# Voeding.net
KiCad netlist of a schematic drawn in Altium Designer
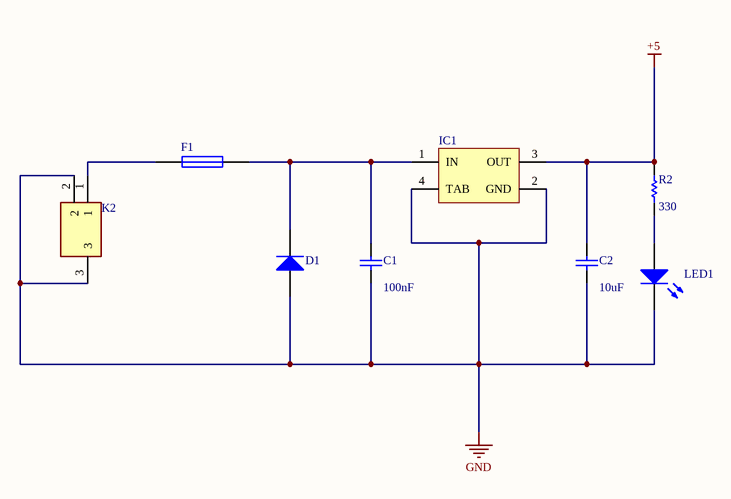
[diagram p0: Voeding.SchDoc]

(export (version "E")
  (design (tool "Eeschema 10.0.6"))
  (components
    (comp (ref "C1")
      (value "100nF")
      (footprint "6-0805_M")
      (description "Capacitor")
      (fields (field (name "Comment") "Cap") (field (name "PUBLISHER") "Altium Limited"))
      (libsource (lib "Miscellaneous Devices") (part "Cap"))
    )
    (comp (ref "C2")
      (value "10uF")
      (footprint "CAP_EEV-FK1K101V")
      (description "Capacitor")
      (fields (field (name "Comment") "Cap") (field (name "PUBLISHER") "Altium Limited"))
      (libsource (lib "Miscellaneous Devices") (part "Cap"))
    )
    (comp (ref "D1")
      (value "Diode 1N4004")
      (footprint "DO-41")
      (description "1 Amp General Purpose Rectifier")
      (fields (field (name "PUBLISHER") "Altium Limited"))
      (libsource (lib "Miscellaneous Devices") (part "Diode 1N4004"))
    )
    (comp (ref "F1")
      (value "Fuse 1")
      (footprint "CAPC3216X94N")
      (description "Fuse")
      (fields (field (name "PUBLISHER") "Altium Limited"))
      (libsource (lib "Miscellaneous Devices") (part "Fuse 1"))
    )
    (comp (ref "IC1")
      (value "LM3940IMP-3.3")
      (footprint "DCY0004A_L")
      (description "1A Low Dropout Regulator for 5V to 3.3V Conversion, 4-pin SOT-223")
      (fields (field (name "MANUFACTURER") "Texas Instruments"))
      (libsource (lib "Altium Content Vault") (part "PM-REG-LM2940-TO4"))
    )
    (comp (ref "K2")
      (value "MJ-180PH")
      (footprint "SamacSys:MJ-180PH")
      (description "Connector")
      (libsource (lib "*") (part "MJ-180PH"))
    )
    (comp (ref "LED1")
      (value "LED0")
      (footprint "LED-0")
      (description "Typical INFRARED GaAs LED")
      (fields (field (name "PUBLISHER") "Altium Limited"))
      (libsource (lib "Miscellaneous Devices") (part "LED0"))
    )
    (comp (ref "R2")
      (value "330")
      (footprint "6-0805_M")
      (description "Resistor")
      (fields (field (name "Comment") "Res1") (field (name "PUBLISHER") "Altium Limited"))
      (libsource (lib "Miscellaneous Devices") (part "Res1"))
    )
  )
  (nets
    (net (code "1") (name "+5") (class "Default")
      (node (ref "C2") (pin "2") (pinfunction "2_2") (pintype "passive"))
      (node (ref "IC1") (pin "3") (pinfunction "OUT_3") (pintype "power_in"))
      (node (ref "R2") (pin "2") (pinfunction "2_2") (pintype "passive"))
    )
    (net (code "2") (name "GND") (class "Default")
      (node (ref "C1") (pin "1") (pinfunction "1_1") (pintype "passive"))
      (node (ref "C2") (pin "1") (pinfunction "1_1") (pintype "passive"))
      (node (ref "D1") (pin "1") (pinfunction "A_1") (pintype "passive"))
      (node (ref "IC1") (pin "2") (pinfunction "GND_2") (pintype "power_in"))
      (node (ref "IC1") (pin "4") (pinfunction "TAB_4") (pintype "power_in"))
      (node (ref "K2") (pin "2") (pinfunction "2_2") (pintype "passive"))
      (node (ref "K2") (pin "3") (pinfunction "3_3") (pintype "passive"))
      (node (ref "LED1") (pin "2") (pinfunction "K_2") (pintype "passive"))
    )
    (net (code "3") (name "Net-(D1-K)") (class "Default")
      (node (ref "C1") (pin "2") (pinfunction "2_2") (pintype "passive"))
      (node (ref "D1") (pin "2") (pinfunction "K_2") (pintype "passive"))
      (node (ref "F1") (pin "2") (pinfunction "2_2") (pintype "passive"))
      (node (ref "IC1") (pin "1") (pinfunction "IN_1") (pintype "power_in"))
    )
    (net (code "4") (name "Net-(F1-Pad1)") (class "Default")
      (node (ref "F1") (pin "1") (pinfunction "1_1") (pintype "passive"))
      (node (ref "K2") (pin "1") (pinfunction "1_1") (pintype "passive"))
    )
    (net (code "5") (name "Net-(LED1-A)") (class "Default")
      (node (ref "LED1") (pin "1") (pinfunction "A_1") (pintype "passive"))
      (node (ref "R2") (pin "1") (pinfunction "1_1") (pintype "passive"))
    )
  )
)
